# Arduino_Board.net
KiCad netlist of a schematic drawn in Altium Designer
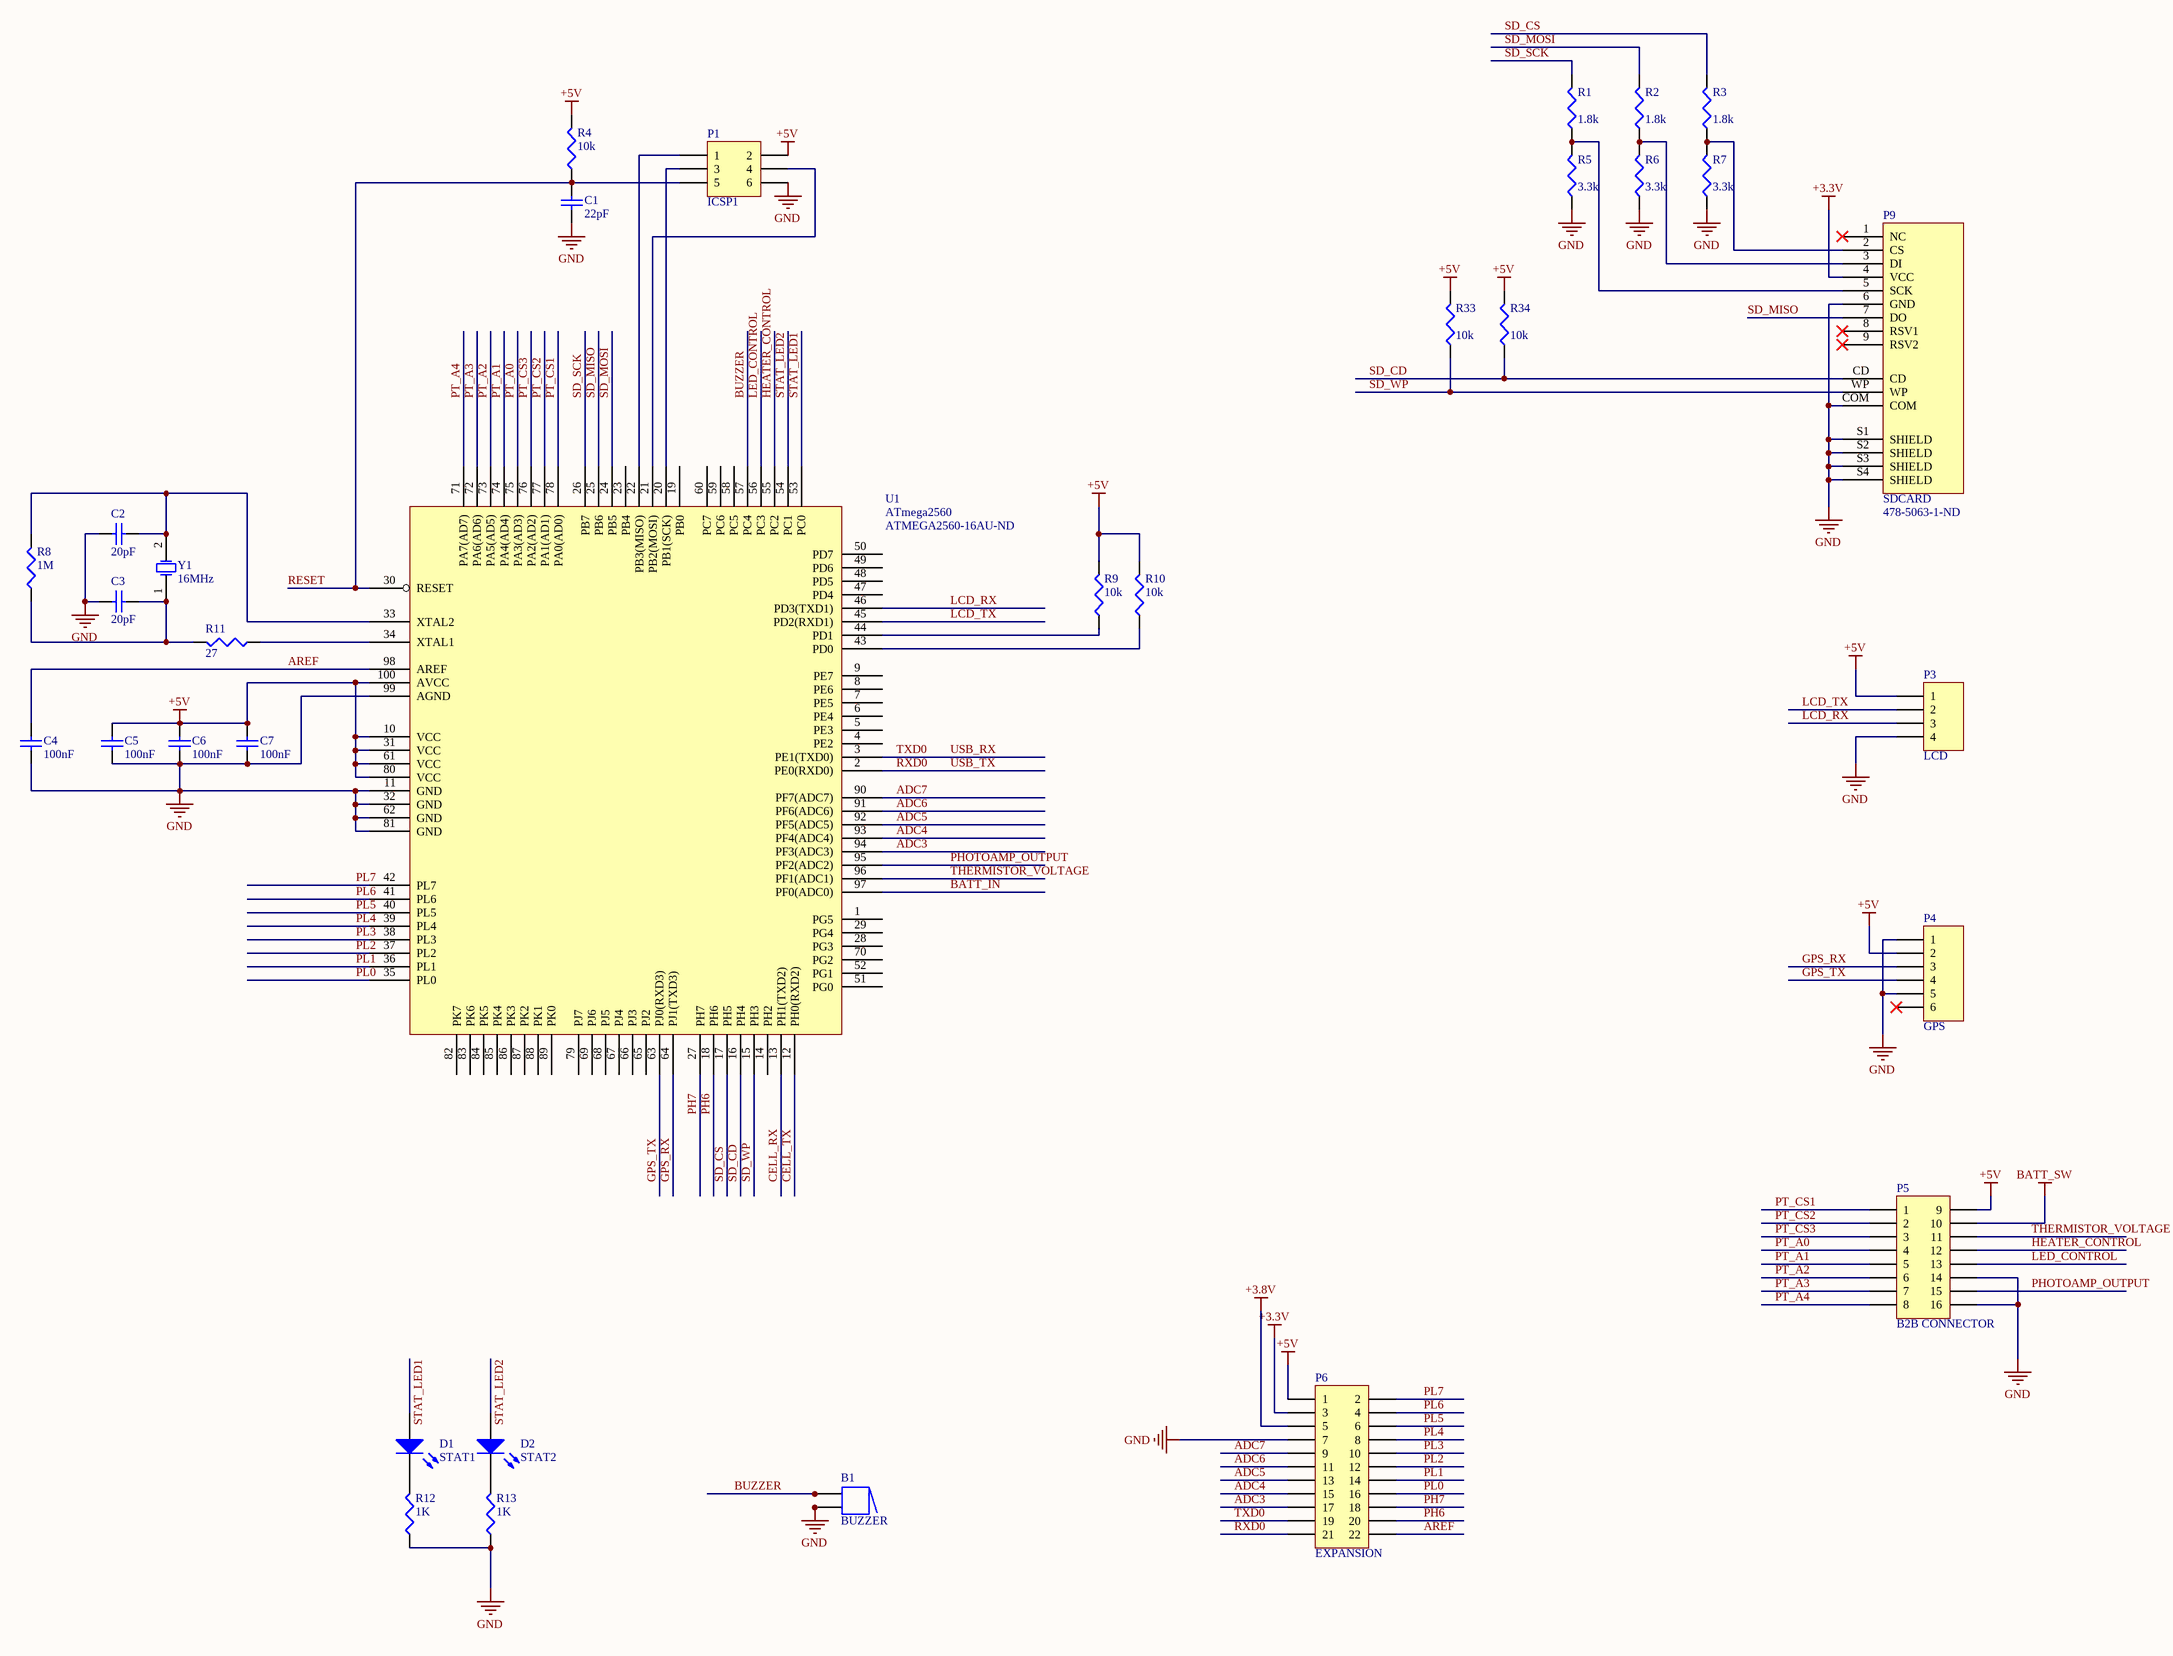
[diagram p0: Arduino Board.SchDoc]

(export (version "E")
  (design (tool "Eeschema 10.0.6"))
  (components
    (comp (ref "B1")
      (value "BUZZER")
      (footprint "BUZZER")
      (description "Magnetic Transducer Buzzer")
      (fields (field (name "PUBLISHER") "Altium Limited"))
      (libsource (lib "Miscellaneous Devices") (part "Buzzer"))
    )
    (comp (ref "C1")
      (value "22pF")
      (footprint "C1206")
      (description "Capacitor (Semiconductor SIM Model)")
      (fields (field (name "Comment") "Cap Semi") (field (name "PUBLISHER") "Altium Limited"))
      (libsource (lib "Miscellaneous Devices") (part "Cap Semi"))
    )
    (comp (ref "C2")
      (value "20pF")
      (footprint "C1206")
      (description "Capacitor (Semiconductor SIM Model)")
      (fields (field (name "Comment") "Cap Semi") (field (name "PUBLISHER") "Altium Limited"))
      (libsource (lib "Miscellaneous Devices") (part "Cap Semi"))
    )
    (comp (ref "C3")
      (value "20pF")
      (footprint "C1206")
      (description "Capacitor (Semiconductor SIM Model)")
      (fields (field (name "Comment") "Cap Semi") (field (name "PUBLISHER") "Altium Limited"))
      (libsource (lib "Miscellaneous Devices") (part "Cap Semi"))
    )
    (comp (ref "C4")
      (value "100nF")
      (footprint "C1206")
      (description "Capacitor (Semiconductor SIM Model)")
      (fields (field (name "Comment") "Cap Semi") (field (name "PUBLISHER") "Altium Limited"))
      (libsource (lib "Miscellaneous Devices") (part "Cap Semi"))
    )
    (comp (ref "C5")
      (value "100nF")
      (footprint "C1206")
      (description "Capacitor (Semiconductor SIM Model)")
      (fields (field (name "Comment") "Cap Semi") (field (name "PUBLISHER") "Altium Limited"))
      (libsource (lib "Miscellaneous Devices") (part "Cap Semi"))
    )
    (comp (ref "C6")
      (value "100nF")
      (footprint "C1206")
      (description "Capacitor (Semiconductor SIM Model)")
      (fields (field (name "Comment") "Cap Semi") (field (name "PUBLISHER") "Altium Limited"))
      (libsource (lib "Miscellaneous Devices") (part "Cap Semi"))
    )
    (comp (ref "C7")
      (value "100nF")
      (footprint "C1206")
      (description "Capacitor (Semiconductor SIM Model)")
      (fields (field (name "Comment") "Cap Semi") (field (name "PUBLISHER") "Altium Limited"))
      (libsource (lib "Miscellaneous Devices") (part "Cap Semi"))
    )
    (comp (ref "D1")
      (value "STAT1")
      (footprint "HDR1X2")
      (description "Typical BLUE SiC LED")
      (fields (field (name "PUBLISHER") "Altium Limited"))
      (libsource (lib "Miscellaneous Devices") (part "LED3"))
    )
    (comp (ref "D2")
      (value "STAT2")
      (footprint "HDR1X2")
      (description "Typical BLUE SiC LED")
      (fields (field (name "PUBLISHER") "Altium Limited"))
      (libsource (lib "Miscellaneous Devices") (part "LED3"))
    )
    (comp (ref "P1")
      (value "ICSP1")
      (footprint "HDR2X3")
      (description "Header, 3-Pin, Dual row")
      (fields (field (name "PUBLISHER") "Altium Limited"))
      (libsource (lib "Miscellaneous Connectors") (part "Header 3X2"))
    )
    (comp (ref "P3")
      (value "LCD")
      (footprint "2MM JST PH - 4 PIN")
      (description "Header, 4-Pin")
      (fields (field (name "PUBLISHER") "Altium Limited"))
      (libsource (lib "Miscellaneous Connectors") (part "Header 4"))
    )
    (comp (ref "P4")
      (value "GPS")
      (footprint "2mm JST PH - 6 pin")
      (description "Header, 6-Pin")
      (fields (field (name "PUBLISHER") "Altium Limited"))
      (libsource (lib "Miscellaneous Connectors") (part "Header 6"))
    )
    (comp (ref "P5")
      (value "B2B CONNECTOR")
      (footprint "HDR2X8_CEN")
      (description "Header, 8-Pin, Dual row")
      (fields (field (name "PUBLISHER") "Altium Limited"))
      (libsource (lib "Miscellaneous Connectors") (part "Header 8X2A"))
    )
    (comp (ref "P6")
      (value "EXPANSION")
      (footprint "HDR2X11")
      (description "Header, 11-Pin, Dual row")
      (fields (field (name "PUBLISHER") "Altium Limited"))
      (libsource (lib "Miscellaneous Connectors") (part "Header 11X2"))
    )
    (comp (ref "P9")
      (value "SDCARD")
      (footprint "SDSLOT")
      (fields (field (name "SUPPLIER PART NUMBER 1") "478-5063-1-ND"))
      (libsource (lib "Altium Footprints") (part "SDSLOT"))
    )
    (comp (ref "R1")
      (value "1.8k")
      (footprint "RESC3216M")
      (description "Resistor")
      (fields (field (name "Comment") "Res3") (field (name "PUBLISHER") "Altium Limited"))
      (libsource (lib "Miscellaneous Devices") (part "Res3"))
    )
    (comp (ref "R2")
      (value "1.8k")
      (footprint "RESC3216M")
      (description "Resistor")
      (fields (field (name "Comment") "Res3") (field (name "PUBLISHER") "Altium Limited"))
      (libsource (lib "Miscellaneous Devices") (part "Res3"))
    )
    (comp (ref "R3")
      (value "1.8k")
      (footprint "RESC3216M")
      (description "Resistor")
      (fields (field (name "Comment") "Res3") (field (name "PUBLISHER") "Altium Limited"))
      (libsource (lib "Miscellaneous Devices") (part "Res3"))
    )
    (comp (ref "R4")
      (value "10k")
      (footprint "RESC3216M")
      (description "Resistor")
      (fields (field (name "Comment") "Res3") (field (name "PUBLISHER") "Altium Limited"))
      (libsource (lib "Miscellaneous Devices") (part "Res3"))
    )
    (comp (ref "R5")
      (value "3.3k")
      (footprint "RESC3216M")
      (description "Resistor")
      (fields (field (name "Comment") "Res3") (field (name "PUBLISHER") "Altium Limited"))
      (libsource (lib "Miscellaneous Devices") (part "Res3"))
    )
    (comp (ref "R6")
      (value "3.3k")
      (footprint "RESC3216M")
      (description "Resistor")
      (fields (field (name "Comment") "Res3") (field (name "PUBLISHER") "Altium Limited"))
      (libsource (lib "Miscellaneous Devices") (part "Res3"))
    )
    (comp (ref "R7")
      (value "3.3k")
      (footprint "RESC3216M")
      (description "Resistor")
      (fields (field (name "Comment") "Res3") (field (name "PUBLISHER") "Altium Limited"))
      (libsource (lib "Miscellaneous Devices") (part "Res3"))
    )
    (comp (ref "R8")
      (value "1M")
      (footprint "RESC3216M")
      (description "Resistor")
      (fields (field (name "Comment") "Res3") (field (name "PUBLISHER") "Altium Limited"))
      (libsource (lib "Miscellaneous Devices") (part "Res3"))
    )
    (comp (ref "R9")
      (value "10k")
      (footprint "RESC3216M")
      (description "Resistor")
      (fields (field (name "Comment") "Res3") (field (name "PUBLISHER") "Altium Limited"))
      (libsource (lib "Miscellaneous Devices") (part "Res3"))
    )
    (comp (ref "R10")
      (value "10k")
      (footprint "RESC3216M")
      (description "Resistor")
      (fields (field (name "Comment") "Res3") (field (name "PUBLISHER") "Altium Limited"))
      (libsource (lib "Miscellaneous Devices") (part "Res3"))
    )
    (comp (ref "R11")
      (value "27")
      (footprint "RESC3216M")
      (description "Resistor")
      (fields (field (name "Comment") "Res3") (field (name "PUBLISHER") "Altium Limited"))
      (libsource (lib "Miscellaneous Devices") (part "Res3"))
    )
    (comp (ref "R12")
      (value "1K")
      (footprint "RESC3216M")
      (description "Resistor")
      (fields (field (name "Comment") "Res3") (field (name "PUBLISHER") "Altium Limited"))
      (libsource (lib "Miscellaneous Devices") (part "Res3"))
    )
    (comp (ref "R13")
      (value "1K")
      (footprint "RESC3216M")
      (description "Resistor")
      (fields (field (name "Comment") "Res3") (field (name "PUBLISHER") "Altium Limited"))
      (libsource (lib "Miscellaneous Devices") (part "Res3"))
    )
    (comp (ref "R33")
      (value "10k")
      (footprint "RESC3216M")
      (description "Resistor")
      (fields (field (name "Comment") "Res3") (field (name "PUBLISHER") "Altium Limited"))
      (libsource (lib "Miscellaneous Devices") (part "Res3"))
    )
    (comp (ref "R34")
      (value "10k")
      (footprint "RESC3216M")
      (description "Resistor")
      (fields (field (name "Comment") "Res3") (field (name "PUBLISHER") "Altium Limited"))
      (libsource (lib "Miscellaneous Devices") (part "Res3"))
    )
    (comp (ref "U1")
      (value "ATmega2560")
      (footprint "TSQFP50P1600X1600-100M")
      (fields (field (name "SUPPLIER PART NUMBER 1") "ATMEGA2560-16AU-ND"))
      (libsource (lib "Altium Footprints") (part "ATmega2560"))
    )
    (comp (ref "Y1")
      (value "16MHz")
      (footprint "SMT Crystal")
      (description "Crystal Oscillator")
      (fields (field (name "PUBLISHER") "Altium Limited"))
      (libsource (lib "Miscellaneous Devices") (part "XTAL"))
    )
  )
  (nets
    (net (code "1") (name "+3.3V") (class "Default")
      (node (ref "P6") (pin "3") (pinfunction "3_3") (pintype "passive"))
      (node (ref "P9") (pin "4") (pinfunction "VCC_4") (pintype "passive"))
    )
    (net (code "2") (name "+3.8V") (class "Default")
      (node (ref "P6") (pin "5") (pinfunction "5_5") (pintype "passive"))
    )
    (net (code "3") (name "+5V") (class "Default")
      (node (ref "C5") (pin "2") (pinfunction "2_2") (pintype "passive"))
      (node (ref "C6") (pin "2") (pinfunction "2_2") (pintype "passive"))
      (node (ref "C7") (pin "2") (pinfunction "2_2") (pintype "passive"))
      (node (ref "P1") (pin "2") (pinfunction "2_2") (pintype "passive"))
      (node (ref "P3") (pin "1") (pinfunction "1_1") (pintype "passive"))
      (node (ref "P4") (pin "2") (pinfunction "2_2") (pintype "passive"))
      (node (ref "P5") (pin "9") (pinfunction "9_9") (pintype "passive"))
      (node (ref "P6") (pin "1") (pinfunction "1_1") (pintype "passive"))
      (node (ref "R10") (pin "2") (pinfunction "2_2") (pintype "passive"))
      (node (ref "R33") (pin "2") (pinfunction "2_2") (pintype "passive"))
      (node (ref "R34") (pin "2") (pinfunction "2_2") (pintype "passive"))
      (node (ref "R4") (pin "2") (pinfunction "2_2") (pintype "passive"))
      (node (ref "R9") (pin "2") (pinfunction "2_2") (pintype "passive"))
      (node (ref "U1") (pin "10") (pinfunction "VCC_10") (pintype "passive"))
      (node (ref "U1") (pin "100") (pinfunction "AVCC_100") (pintype "passive"))
      (node (ref "U1") (pin "31") (pinfunction "VCC_31") (pintype "passive"))
      (node (ref "U1") (pin "61") (pinfunction "VCC_61") (pintype "passive"))
      (node (ref "U1") (pin "80") (pinfunction "VCC_80") (pintype "passive"))
    )
    (net (code "4") (name "/ADC3") (class "Default")
      (node (ref "P6") (pin "17") (pinfunction "17_17") (pintype "passive"))
      (node (ref "U1") (pin "94") (pinfunction "PF3(ADC3)_94") (pintype "passive"))
    )
    (net (code "5") (name "/ADC4") (class "Default")
      (node (ref "P6") (pin "15") (pinfunction "15_15") (pintype "passive"))
      (node (ref "U1") (pin "93") (pinfunction "PF4(ADC4)_93") (pintype "passive"))
    )
    (net (code "6") (name "/ADC5") (class "Default")
      (node (ref "P6") (pin "13") (pinfunction "13_13") (pintype "passive"))
      (node (ref "U1") (pin "92") (pinfunction "PF5(ADC5)_92") (pintype "passive"))
    )
    (net (code "7") (name "/ADC6") (class "Default")
      (node (ref "P6") (pin "11") (pinfunction "11_11") (pintype "passive"))
      (node (ref "U1") (pin "91") (pinfunction "PF6(ADC6)_91") (pintype "passive"))
    )
    (net (code "8") (name "/ADC7") (class "Default")
      (node (ref "P6") (pin "9") (pinfunction "9_9") (pintype "passive"))
      (node (ref "U1") (pin "90") (pinfunction "PF7(ADC7)_90") (pintype "passive"))
    )
    (net (code "9") (name "/AREF") (class "Default")
      (node (ref "C4") (pin "2") (pinfunction "2_2") (pintype "passive"))
      (node (ref "P6") (pin "22") (pinfunction "22_22") (pintype "passive"))
      (node (ref "U1") (pin "98") (pinfunction "AREF_98") (pintype "passive"))
    )
    (net (code "10") (name "/BATT_IN") (class "Default")
      (node (ref "U1") (pin "97") (pinfunction "PF0(ADC0)_97") (pintype "passive"))
    )
    (net (code "11") (name "/BUZZER") (class "Default")
      (node (ref "B1") (pin "1") (pinfunction "1_1") (pintype "passive"))
      (node (ref "B1") (pin "1A") (pinfunction "1A_1A") (pintype "passive"))
      (node (ref "U1") (pin "57") (pinfunction "PC4_57") (pintype "passive"))
    )
    (net (code "12") (name "/CELL_RX") (class "Default")
      (node (ref "U1") (pin "13") (pinfunction "PH1(TXD2)_13") (pintype "passive"))
    )
    (net (code "13") (name "/CELL_TX") (class "Default")
      (node (ref "U1") (pin "12") (pinfunction "PH0(RXD2)_12") (pintype "passive"))
    )
    (net (code "14") (name "/GPS_RX") (class "Default")
      (node (ref "P4") (pin "3") (pinfunction "3_3") (pintype "passive"))
      (node (ref "U1") (pin "64") (pinfunction "PJ1(TXD3)_64") (pintype "passive"))
    )
    (net (code "15") (name "/GPS_TX") (class "Default")
      (node (ref "P4") (pin "4") (pinfunction "4_4") (pintype "passive"))
      (node (ref "U1") (pin "63") (pinfunction "PJ0(RXD3)_63") (pintype "passive"))
    )
    (net (code "16") (name "/HEATER_CONTROL") (class "Default")
      (node (ref "P5") (pin "12") (pinfunction "12_12") (pintype "passive"))
      (node (ref "U1") (pin "55") (pinfunction "PC2_55") (pintype "passive"))
    )
    (net (code "17") (name "/LCD_RX") (class "Default")
      (node (ref "P3") (pin "3") (pinfunction "3_3") (pintype "passive"))
      (node (ref "U1") (pin "46") (pinfunction "PD3(TXD1)_46") (pintype "passive"))
    )
    (net (code "18") (name "/LCD_TX") (class "Default")
      (node (ref "P3") (pin "2") (pinfunction "2_2") (pintype "passive"))
      (node (ref "U1") (pin "45") (pinfunction "PD2(RXD1)_45") (pintype "passive"))
    )
    (net (code "19") (name "/LED_CONTROL") (class "Default")
      (node (ref "P5") (pin "13") (pinfunction "13_13") (pintype "passive"))
      (node (ref "U1") (pin "56") (pinfunction "PC3_56") (pintype "passive"))
    )
    (net (code "20") (name "/PH6") (class "Default")
      (node (ref "P6") (pin "20") (pinfunction "20_20") (pintype "passive"))
      (node (ref "U1") (pin "18") (pinfunction "PH6_18") (pintype "passive"))
    )
    (net (code "21") (name "/PH7") (class "Default")
      (node (ref "P6") (pin "18") (pinfunction "18_18") (pintype "passive"))
      (node (ref "U1") (pin "27") (pinfunction "PH7_27") (pintype "passive"))
    )
    (net (code "22") (name "/PHOTOAMP_OUTPUT") (class "Default")
      (node (ref "P5") (pin "15") (pinfunction "15_15") (pintype "passive"))
      (node (ref "U1") (pin "95") (pinfunction "PF2(ADC2)_95") (pintype "passive"))
    )
    (net (code "23") (name "/PL0") (class "Default")
      (node (ref "P6") (pin "16") (pinfunction "16_16") (pintype "passive"))
      (node (ref "U1") (pin "35") (pinfunction "PL0_35") (pintype "passive"))
    )
    (net (code "24") (name "/PL1") (class "Default")
      (node (ref "P6") (pin "14") (pinfunction "14_14") (pintype "passive"))
      (node (ref "U1") (pin "36") (pinfunction "PL1_36") (pintype "passive"))
    )
    (net (code "25") (name "/PL2") (class "Default")
      (node (ref "P6") (pin "12") (pinfunction "12_12") (pintype "passive"))
      (node (ref "U1") (pin "37") (pinfunction "PL2_37") (pintype "passive"))
    )
    (net (code "26") (name "/PL3") (class "Default")
      (node (ref "P6") (pin "10") (pinfunction "10_10") (pintype "passive"))
      (node (ref "U1") (pin "38") (pinfunction "PL3_38") (pintype "passive"))
    )
    (net (code "27") (name "/PL4") (class "Default")
      (node (ref "P6") (pin "8") (pinfunction "8_8") (pintype "passive"))
      (node (ref "U1") (pin "39") (pinfunction "PL4_39") (pintype "passive"))
    )
    (net (code "28") (name "/PL5") (class "Default")
      (node (ref "P6") (pin "6") (pinfunction "6_6") (pintype "passive"))
      (node (ref "U1") (pin "40") (pinfunction "PL5_40") (pintype "passive"))
    )
    (net (code "29") (name "/PL6") (class "Default")
      (node (ref "P6") (pin "4") (pinfunction "4_4") (pintype "passive"))
      (node (ref "U1") (pin "41") (pinfunction "PL6_41") (pintype "passive"))
    )
    (net (code "30") (name "/PL7") (class "Default")
      (node (ref "P6") (pin "2") (pinfunction "2_2") (pintype "passive"))
      (node (ref "U1") (pin "42") (pinfunction "PL7_42") (pintype "passive"))
    )
    (net (code "31") (name "/PT_A0") (class "Default")
      (node (ref "P5") (pin "4") (pinfunction "4_4") (pintype "passive"))
      (node (ref "U1") (pin "75") (pinfunction "PA3(AD3)_75") (pintype "passive"))
    )
    (net (code "32") (name "/PT_A1") (class "Default")
      (node (ref "P5") (pin "5") (pinfunction "5_5") (pintype "passive"))
      (node (ref "U1") (pin "74") (pinfunction "PA4(AD4)_74") (pintype "passive"))
    )
    (net (code "33") (name "/PT_A2") (class "Default")
      (node (ref "P5") (pin "6") (pinfunction "6_6") (pintype "passive"))
      (node (ref "U1") (pin "73") (pinfunction "PA5(AD5)_73") (pintype "passive"))
    )
    (net (code "34") (name "/PT_A3") (class "Default")
      (node (ref "P5") (pin "7") (pinfunction "7_7") (pintype "passive"))
      (node (ref "U1") (pin "72") (pinfunction "PA6(AD6)_72") (pintype "passive"))
    )
    (net (code "35") (name "/PT_A4") (class "Default")
      (node (ref "P5") (pin "8") (pinfunction "8_8") (pintype "passive"))
      (node (ref "U1") (pin "71") (pinfunction "PA7(AD7)_71") (pintype "passive"))
    )
    (net (code "36") (name "/PT_CS1") (class "Default")
      (node (ref "P5") (pin "1") (pinfunction "1_1") (pintype "passive"))
      (node (ref "U1") (pin "78") (pinfunction "PA0(AD0)_78") (pintype "passive"))
    )
    (net (code "37") (name "/PT_CS2") (class "Default")
      (node (ref "P5") (pin "2") (pinfunction "2_2") (pintype "passive"))
      (node (ref "U1") (pin "77") (pinfunction "PA1(AD1)_77") (pintype "passive"))
    )
    (net (code "38") (name "/PT_CS3") (class "Default")
      (node (ref "P5") (pin "3") (pinfunction "3_3") (pintype "passive"))
      (node (ref "U1") (pin "76") (pinfunction "PA2(AD2)_76") (pintype "passive"))
    )
    (net (code "39") (name "/RESET") (class "Default")
      (node (ref "C1") (pin "2") (pinfunction "2_2") (pintype "passive"))
      (node (ref "P1") (pin "5") (pinfunction "5_5") (pintype "passive"))
      (node (ref "R4") (pin "1") (pinfunction "1_1") (pintype "passive"))
      (node (ref "U1") (pin "30") (pinfunction "RESET_30") (pintype "passive"))
    )
    (net (code "40") (name "/RXD0") (class "Default")
      (node (ref "P6") (pin "21") (pinfunction "21_21") (pintype "passive"))
      (node (ref "U1") (pin "2") (pinfunction "PE0(RXD0)_2") (pintype "passive"))
    )
    (net (code "41") (name "/SD_CD") (class "Default")
      (node (ref "P9") (pin "CD") (pinfunction "CD_CD") (pintype "passive"))
      (node (ref "R34") (pin "1") (pinfunction "1_1") (pintype "passive"))
      (node (ref "U1") (pin "16") (pinfunction "PH4_16") (pintype "passive"))
    )
    (net (code "42") (name "/SD_CS") (class "Default")
      (node (ref "R3") (pin "2") (pinfunction "2_2") (pintype "passive"))
      (node (ref "U1") (pin "17") (pinfunction "PH5_17") (pintype "passive"))
    )
    (net (code "43") (name "/SD_MISO") (class "Default")
      (node (ref "P9") (pin "7") (pinfunction "DO_7") (pintype "passive"))
      (node (ref "U1") (pin "25") (pinfunction "PB6_25") (pintype "passive"))
    )
    (net (code "44") (name "/SD_MOSI") (class "Default")
      (node (ref "R2") (pin "2") (pinfunction "2_2") (pintype "passive"))
      (node (ref "U1") (pin "24") (pinfunction "PB5_24") (pintype "passive"))
    )
    (net (code "45") (name "/SD_SCK") (class "Default")
      (node (ref "R1") (pin "2") (pinfunction "2_2") (pintype "passive"))
      (node (ref "U1") (pin "26") (pinfunction "PB7_26") (pintype "passive"))
    )
    (net (code "46") (name "/SD_WP") (class "Default")
      (node (ref "P9") (pin "WP") (pinfunction "WP_WP") (pintype "passive"))
      (node (ref "R33") (pin "1") (pinfunction "1_1") (pintype "passive"))
      (node (ref "U1") (pin "15") (pinfunction "PH3_15") (pintype "passive"))
    )
    (net (code "47") (name "/STAT_LED1") (class "Default")
      (node (ref "D1") (pin "1") (pinfunction "A_1") (pintype "passive"))
      (node (ref "U1") (pin "53") (pinfunction "PC0_53") (pintype "passive"))
    )
    (net (code "48") (name "/STAT_LED2") (class "Default")
      (node (ref "D2") (pin "1") (pinfunction "A_1") (pintype "passive"))
      (node (ref "U1") (pin "54") (pinfunction "PC1_54") (pintype "passive"))
    )
    (net (code "49") (name "/THERMISTOR_VOLTAGE") (class "Default")
      (node (ref "P5") (pin "11") (pinfunction "11_11") (pintype "passive"))
      (node (ref "U1") (pin "96") (pinfunction "PF1(ADC1)_96") (pintype "passive"))
    )
    (net (code "50") (name "/TXD0") (class "Default")
      (node (ref "P6") (pin "19") (pinfunction "19_19") (pintype "passive"))
      (node (ref "U1") (pin "3") (pinfunction "PE1(TXD0)_3") (pintype "passive"))
    )
    (net (code "51") (name "BATT_SW") (class "Default")
      (node (ref "P5") (pin "10") (pinfunction "10_10") (pintype "passive"))
    )
    (net (code "52") (name "GND") (class "Default")
      (node (ref "B1") (pin "2") (pinfunction "2_2") (pintype "passive"))
      (node (ref "B1") (pin "2A") (pinfunction "2A_2A") (pintype "passive"))
      (node (ref "C1") (pin "1") (pinfunction "1_1") (pintype "passive"))
      (node (ref "C2") (pin "1") (pinfunction "1_1") (pintype "passive"))
      (node (ref "C3") (pin "2") (pinfunction "2_2") (pintype "passive"))
      (node (ref "C4") (pin "1") (pinfunction "1_1") (pintype "passive"))
      (node (ref "C5") (pin "1") (pinfunction "1_1") (pintype "passive"))
      (node (ref "C6") (pin "1") (pinfunction "1_1") (pintype "passive"))
      (node (ref "C7") (pin "1") (pinfunction "1_1") (pintype "passive"))
      (node (ref "P1") (pin "6") (pinfunction "6_6") (pintype "passive"))
      (node (ref "P3") (pin "4") (pinfunction "4_4") (pintype "passive"))
      (node (ref "P4") (pin "1") (pinfunction "1_1") (pintype "passive"))
      (node (ref "P4") (pin "5") (pinfunction "5_5") (pintype "passive"))
      (node (ref "P5") (pin "14") (pinfunction "14_14") (pintype "passive"))
      (node (ref "P5") (pin "16") (pinfunction "16_16") (pintype "passive"))
      (node (ref "P6") (pin "7") (pinfunction "7_7") (pintype "passive"))
      (node (ref "P9") (pin "6") (pinfunction "GND_6") (pintype "passive"))
      (node (ref "P9") (pin "COM") (pinfunction "COM_COM") (pintype "passive"))
      (node (ref "P9") (pin "S1") (pinfunction "SHIELD_S1") (pintype "passive"))
      (node (ref "P9") (pin "S2") (pinfunction "SHIELD_S2") (pintype "passive"))
      (node (ref "P9") (pin "S3") (pinfunction "SHIELD_S3") (pintype "passive"))
      (node (ref "P9") (pin "S4") (pinfunction "SHIELD_S4") (pintype "passive"))
      (node (ref "R12") (pin "1") (pinfunction "1_1") (pintype "passive"))
      (node (ref "R13") (pin "1") (pinfunction "1_1") (pintype "passive"))
      (node (ref "R5") (pin "1") (pinfunction "1_1") (pintype "passive"))
      (node (ref "R6") (pin "1") (pinfunction "1_1") (pintype "passive"))
      (node (ref "R7") (pin "1") (pinfunction "1_1") (pintype "passive"))
      (node (ref "U1") (pin "11") (pinfunction "GND_11") (pintype "passive"))
      (node (ref "U1") (pin "32") (pinfunction "GND_32") (pintype "passive"))
      (node (ref "U1") (pin "62") (pinfunction "GND_62") (pintype "passive"))
      (node (ref "U1") (pin "81") (pinfunction "GND_81") (pintype "passive"))
      (node (ref "U1") (pin "99") (pinfunction "AGND_99") (pintype "passive"))
    )
    (net (code "53") (name "Net-(D1-K)") (class "Default")
      (node (ref "D1") (pin "2") (pinfunction "K_2") (pintype "passive"))
      (node (ref "R12") (pin "2") (pinfunction "2_2") (pintype "passive"))
    )
    (net (code "54") (name "Net-(D2-K)") (class "Default")
      (node (ref "D2") (pin "2") (pinfunction "K_2") (pintype "passive"))
      (node (ref "R13") (pin "2") (pinfunction "2_2") (pintype "passive"))
    )
    (net (code "55") (name "Net-(P9-CS)") (class "Default")
      (node (ref "P9") (pin "2") (pinfunction "CS_2") (pintype "passive"))
      (node (ref "R3") (pin "1") (pinfunction "1_1") (pintype "passive"))
      (node (ref "R7") (pin "2") (pinfunction "2_2") (pintype "passive"))
    )
    (net (code "56") (name "Net-(P9-DI)") (class "Default")
      (node (ref "P9") (pin "3") (pinfunction "DI_3") (pintype "passive"))
      (node (ref "R2") (pin "1") (pinfunction "1_1") (pintype "passive"))
      (node (ref "R6") (pin "2") (pinfunction "2_2") (pintype "passive"))
    )
    (net (code "57") (name "Net-(P9-SCK)") (class "Default")
      (node (ref "P9") (pin "5") (pinfunction "SCK_5") (pintype "passive"))
      (node (ref "R1") (pin "1") (pinfunction "1_1") (pintype "passive"))
      (node (ref "R5") (pin "2") (pinfunction "2_2") (pintype "passive"))
    )
    (net (code "58") (name "Net-(U1-PB1(SCK))") (class "Default")
      (node (ref "P1") (pin "3") (pinfunction "3_3") (pintype "passive"))
      (node (ref "U1") (pin "20") (pinfunction "PB1(SCK)_20") (pintype "passive"))
    )
    (net (code "59") (name "Net-(U1-PB2(MOSI))") (class "Default")
      (node (ref "P1") (pin "4") (pinfunction "4_4") (pintype "passive"))
      (node (ref "U1") (pin "21") (pinfunction "PB2(MOSI)_21") (pintype "passive"))
    )
    (net (code "60") (name "Net-(U1-PB3(MISO))") (class "Default")
      (node (ref "P1") (pin "1") (pinfunction "1_1") (pintype "passive"))
      (node (ref "U1") (pin "22") (pinfunction "PB3(MISO)_22") (pintype "passive"))
    )
    (net (code "61") (name "Net-(U1-PD0)") (class "Default")
      (node (ref "R10") (pin "1") (pinfunction "1_1") (pintype "passive"))
      (node (ref "U1") (pin "43") (pinfunction "PD0_43") (pintype "passive"))
    )
    (net (code "62") (name "Net-(U1-PD1)") (class "Default")
      (node (ref "R9") (pin "1") (pinfunction "1_1") (pintype "passive"))
      (node (ref "U1") (pin "44") (pinfunction "PD1_44") (pintype "passive"))
    )
    (net (code "63") (name "Net-(U1-XTAL1)") (class "Default")
      (node (ref "R11") (pin "1") (pinfunction "1_1") (pintype "passive"))
      (node (ref "U1") (pin "34") (pinfunction "XTAL1_34") (pintype "passive"))
    )
    (net (code "64") (name "Net-(U1-XTAL2)") (class "Default")
      (node (ref "C2") (pin "2") (pinfunction "2_2") (pintype "passive"))
      (node (ref "R8") (pin "2") (pinfunction "2_2") (pintype "passive"))
      (node (ref "U1") (pin "33") (pinfunction "XTAL2_33") (pintype "passive"))
      (node (ref "Y1") (pin "2") (pinfunction "OSC2_2") (pintype "passive"))
    )
    (net (code "65") (name "Net-(Y1-OSC1)") (class "Default")
      (node (ref "C3") (pin "1") (pinfunction "1_1") (pintype "passive"))
      (node (ref "R11") (pin "2") (pinfunction "2_2") (pintype "passive"))
      (node (ref "R8") (pin "1") (pinfunction "1_1") (pintype "passive"))
      (node (ref "Y1") (pin "1") (pinfunction "OSC1_1") (pintype "passive"))
    )
    (net (code "66") (name "unconnected-(P4-Pad6)") (class "Default")
      (node (ref "P4") (pin "6") (pinfunction "6_6") (pintype "passive+no_connect"))
    )
    (net (code "67") (name "unconnected-(P9-NC-Pad1)") (class "Default")
      (node (ref "P9") (pin "1") (pinfunction "NC_1") (pintype "passive+no_connect"))
    )
    (net (code "68") (name "unconnected-(P9-RSV1-Pad8)") (class "Default")
      (node (ref "P9") (pin "8") (pinfunction "RSV1_8") (pintype "passive+no_connect"))
    )
    (net (code "69") (name "unconnected-(P9-RSV2-Pad9)") (class "Default")
      (node (ref "P9") (pin "9") (pinfunction "RSV2_9") (pintype "passive+no_connect"))
    )
    (net (code "70") (name "unconnected-(U1-PB0-Pad19)") (class "Default")
      (node (ref "U1") (pin "19") (pinfunction "PB0_19") (pintype "passive"))
    )
    (net (code "71") (name "unconnected-(U1-PB4-Pad23)") (class "Default")
      (node (ref "U1") (pin "23") (pinfunction "PB4_23") (pintype "passive"))
    )
    (net (code "72") (name "unconnected-(U1-PC5-Pad58)") (class "Default")
      (node (ref "U1") (pin "58") (pinfunction "PC5_58") (pintype "passive"))
    )
    (net (code "73") (name "unconnected-(U1-PC6-Pad59)") (class "Default")
      (node (ref "U1") (pin "59") (pinfunction "PC6_59") (pintype "passive"))
    )
    (net (code "74") (name "unconnected-(U1-PC7-Pad60)") (class "Default")
      (node (ref "U1") (pin "60") (pinfunction "PC7_60") (pintype "passive"))
    )
    (net (code "75") (name "unconnected-(U1-PD4-Pad47)") (class "Default")
      (node (ref "U1") (pin "47") (pinfunction "PD4_47") (pintype "passive"))
    )
    (net (code "76") (name "unconnected-(U1-PD5-Pad48)") (class "Default")
      (node (ref "U1") (pin "48") (pinfunction "PD5_48") (pintype "passive"))
    )
    (net (code "77") (name "unconnected-(U1-PD6-Pad49)") (class "Default")
      (node (ref "U1") (pin "49") (pinfunction "PD6_49") (pintype "passive"))
    )
    (net (code "78") (name "unconnected-(U1-PD7-Pad50)") (class "Default")
      (node (ref "U1") (pin "50") (pinfunction "PD7_50") (pintype "passive"))
    )
    (net (code "79") (name "unconnected-(U1-PE2-Pad4)") (class "Default")
      (node (ref "U1") (pin "4") (pinfunction "PE2_4") (pintype "passive"))
    )
    (net (code "80") (name "unconnected-(U1-PE3-Pad5)") (class "Default")
      (node (ref "U1") (pin "5") (pinfunction "PE3_5") (pintype "passive"))
    )
    (net (code "81") (name "unconnected-(U1-PE4-Pad6)") (class "Default")
      (node (ref "U1") (pin "6") (pinfunction "PE4_6") (pintype "passive"))
    )
    (net (code "82") (name "unconnected-(U1-PE5-Pad7)") (class "Default")
      (node (ref "U1") (pin "7") (pinfunction "PE5_7") (pintype "passive"))
    )
    (net (code "83") (name "unconnected-(U1-PE6-Pad8)") (class "Default")
      (node (ref "U1") (pin "8") (pinfunction "PE6_8") (pintype "passive"))
    )
    (net (code "84") (name "unconnected-(U1-PE7-Pad9)") (class "Default")
      (node (ref "U1") (pin "9") (pinfunction "PE7_9") (pintype "passive"))
    )
    (net (code "85") (name "unconnected-(U1-PG0-Pad51)") (class "Default")
      (node (ref "U1") (pin "51") (pinfunction "PG0_51") (pintype "passive"))
    )
    (net (code "86") (name "unconnected-(U1-PG1-Pad52)") (class "Default")
      (node (ref "U1") (pin "52") (pinfunction "PG1_52") (pintype "passive"))
    )
    (net (code "87") (name "unconnected-(U1-PG2-Pad70)") (class "Default")
      (node (ref "U1") (pin "70") (pinfunction "PG2_70") (pintype "passive"))
    )
    (net (code "88") (name "unconnected-(U1-PG3-Pad28)") (class "Default")
      (node (ref "U1") (pin "28") (pinfunction "PG3_28") (pintype "passive"))
    )
    (net (code "89") (name "unconnected-(U1-PG4-Pad29)") (class "Default")
      (node (ref "U1") (pin "29") (pinfunction "PG4_29") (pintype "passive"))
    )
    (net (code "90") (name "unconnected-(U1-PG5-Pad1)") (class "Default")
      (node (ref "U1") (pin "1") (pinfunction "PG5_1") (pintype "passive"))
    )
    (net (code "91") (name "unconnected-(U1-PH2-Pad14)") (class "Default")
      (node (ref "U1") (pin "14") (pinfunction "PH2_14") (pintype "passive"))
    )
    (net (code "92") (name "unconnected-(U1-PJ2-Pad65)") (class "Default")
      (node (ref "U1") (pin "65") (pinfunction "PJ2_65") (pintype "passive"))
    )
    (net (code "93") (name "unconnected-(U1-PJ3-Pad66)") (class "Default")
      (node (ref "U1") (pin "66") (pinfunction "PJ3_66") (pintype "passive"))
    )
    (net (code "94") (name "unconnected-(U1-PJ4-Pad67)") (class "Default")
      (node (ref "U1") (pin "67") (pinfunction "PJ4_67") (pintype "passive"))
    )
    (net (code "95") (name "unconnected-(U1-PJ5-Pad68)") (class "Default")
      (node (ref "U1") (pin "68") (pinfunction "PJ5_68") (pintype "passive"))
    )
    (net (code "96") (name "unconnected-(U1-PJ6-Pad69)") (class "Default")
      (node (ref "U1") (pin "69") (pinfunction "PJ6_69") (pintype "passive"))
    )
    (net (code "97") (name "unconnected-(U1-PJ7-Pad79)") (class "Default")
      (node (ref "U1") (pin "79") (pinfunction "PJ7_79") (pintype "passive"))
    )
    (net (code "98") (name "unconnected-(U1-PK0-Pad89)") (class "Default")
      (node (ref "U1") (pin "89") (pinfunction "PK0_89") (pintype "passive"))
    )
    (net (code "99") (name "unconnected-(U1-PK1-Pad88)") (class "Default")
      (node (ref "U1") (pin "88") (pinfunction "PK1_88") (pintype "passive"))
    )
    (net (code "100") (name "unconnected-(U1-PK2-Pad87)") (class "Default")
      (node (ref "U1") (pin "87") (pinfunction "PK2_87") (pintype "passive"))
    )
    (net (code "101") (name "unconnected-(U1-PK3-Pad86)") (class "Default")
      (node (ref "U1") (pin "86") (pinfunction "PK3_86") (pintype "passive"))
    )
    (net (code "102") (name "unconnected-(U1-PK4-Pad85)") (class "Default")
      (node (ref "U1") (pin "85") (pinfunction "PK4_85") (pintype "passive"))
    )
    (net (code "103") (name "unconnected-(U1-PK5-Pad84)") (class "Default")
      (node (ref "U1") (pin "84") (pinfunction "PK5_84") (pintype "passive"))
    )
    (net (code "104") (name "unconnected-(U1-PK6-Pad83)") (class "Default")
      (node (ref "U1") (pin "83") (pinfunction "PK6_83") (pintype "passive"))
    )
    (net (code "105") (name "unconnected-(U1-PK7-Pad82)") (class "Default")
      (node (ref "U1") (pin "82") (pinfunction "PK7_82") (pintype "passive"))
    )
  )
)
